# 23Octubre.net
KiCad netlist of a schematic drawn in EAGLE
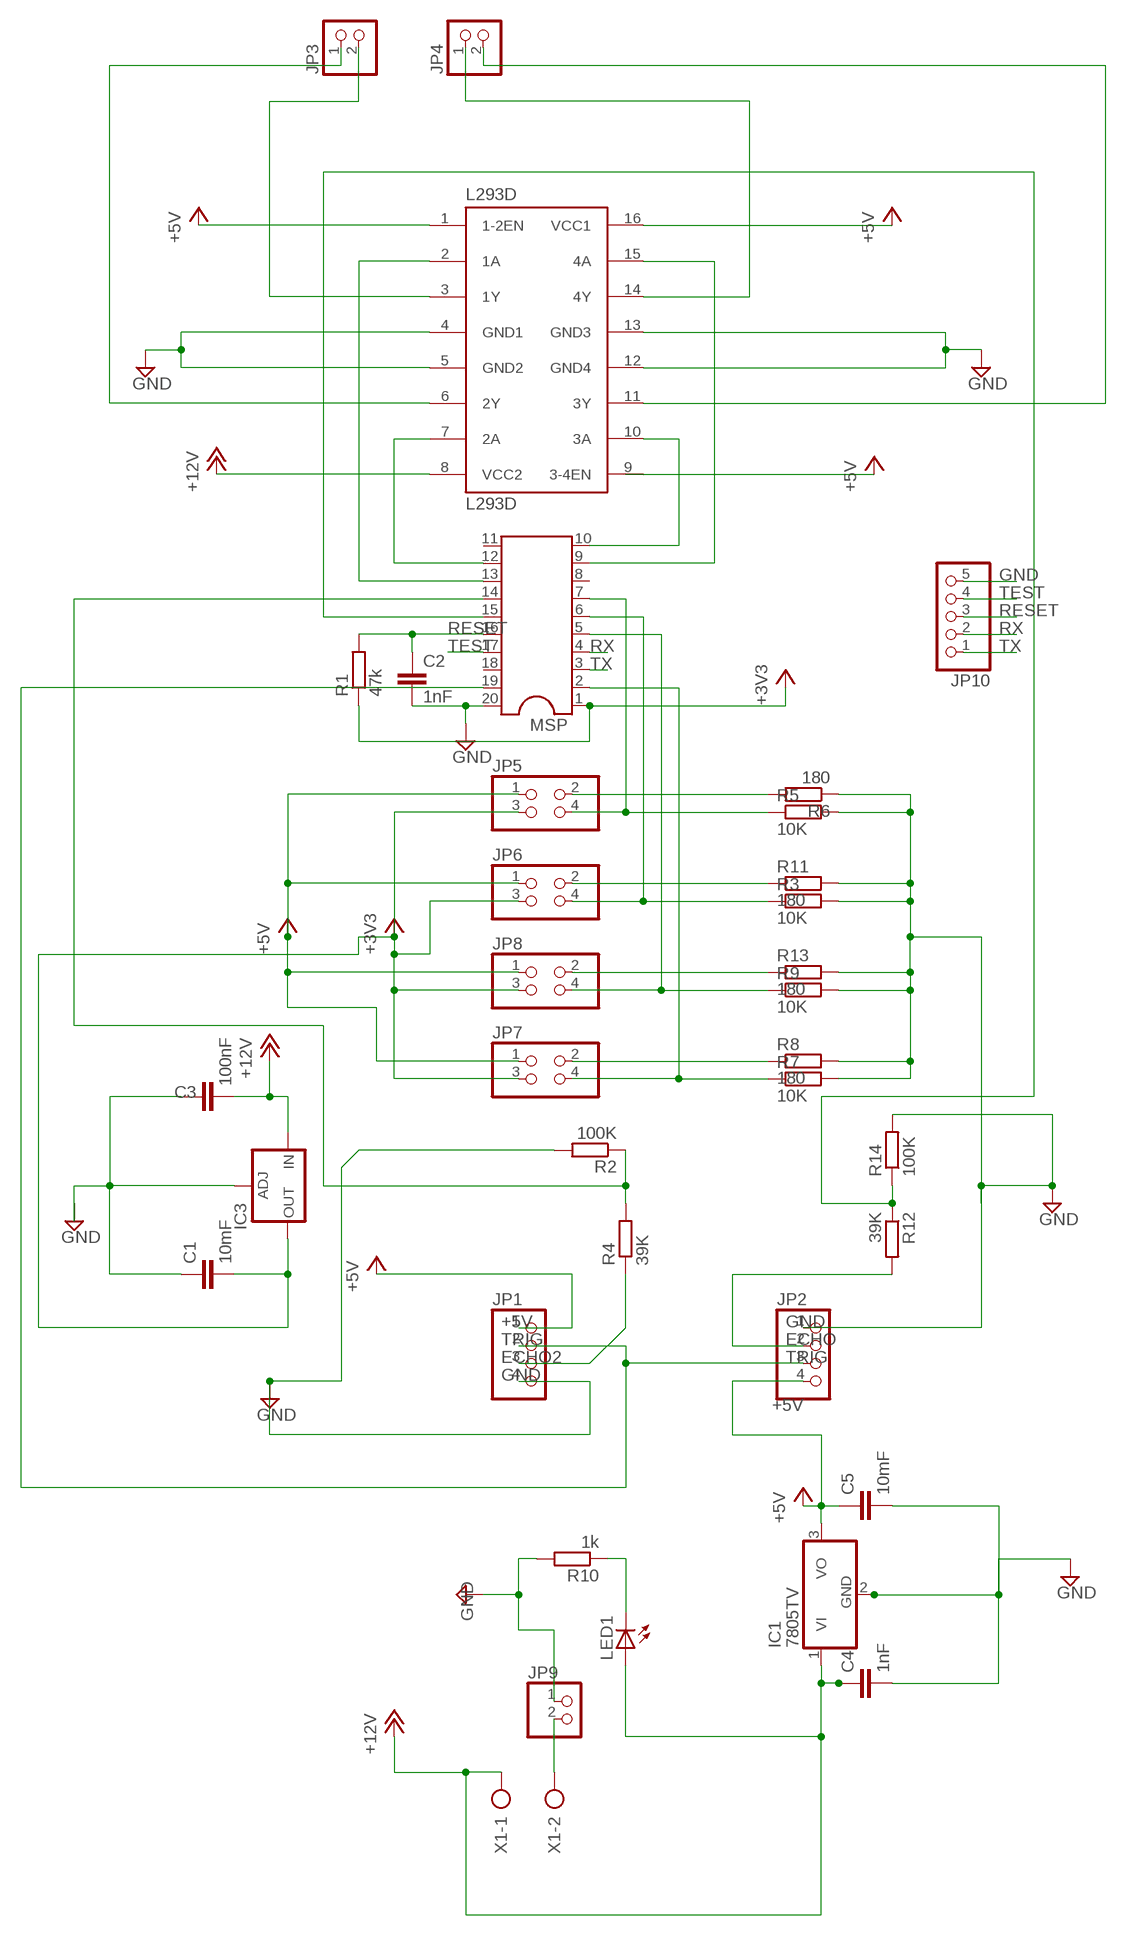
[diagram p0: schematic, sheet 1]

(export (version "E")
  (design (tool "Eeschema 10.0.6"))
  (components
    (comp (ref "C1")
      (value "10mF")
      (footprint "eagle-import:C050-025X075")
      (libsource (lib "eagle-import") (part "C-EU050-025X075"))
    )
    (comp (ref "C2")
      (value "1nF")
      (footprint "eagle-import:C050-025X075")
      (libsource (lib "eagle-import") (part "C-EU050-025X075"))
    )
    (comp (ref "C3")
      (value "100nF")
      (footprint "eagle-import:C050-025X075")
      (libsource (lib "eagle-import") (part "C-EU050-025X075"))
    )
    (comp (ref "C4")
      (value "1nF")
      (footprint "eagle-import:C050-025X075")
      (libsource (lib "eagle-import") (part "C-EU050-025X075"))
    )
    (comp (ref "C5")
      (value "10mF")
      (footprint "eagle-import:C050-025X075")
      (libsource (lib "eagle-import") (part "C-EU050-025X075"))
    )
    (comp (ref "IC1")
      (value "7805TV")
      (footprint "eagle-import:TO220V")
      (libsource (lib "eagle-import") (part "78TV05"))
    )
    (comp (ref "IC3")
      (value "LM317TS")
      (footprint "eagle-import:317TS")
      (libsource (lib "eagle-import") (part "LM317TS"))
    )
    (comp (ref "JP1")
      (value "PINHD-1X4")
      (footprint "eagle-import:1X04")
      (libsource (lib "eagle-import") (part "PINHD-1X4"))
    )
    (comp (ref "JP2")
      (value "PINHD-1X4")
      (footprint "eagle-import:1X04")
      (libsource (lib "eagle-import") (part "PINHD-1X4"))
    )
    (comp (ref "JP3")
      (value "PINHD-1X2")
      (footprint "eagle-import:1X02")
      (libsource (lib "eagle-import") (part "PINHD-1X2"))
    )
    (comp (ref "JP4")
      (value "PINHD-1X2")
      (footprint "eagle-import:1X02")
      (libsource (lib "eagle-import") (part "PINHD-1X2"))
    )
    (comp (ref "JP5")
      (value "PINHD-2X2")
      (footprint "eagle-import:2X02")
      (libsource (lib "eagle-import") (part "PINHD-2X2"))
    )
    (comp (ref "JP6")
      (value "PINHD-2X2")
      (footprint "eagle-import:2X02")
      (libsource (lib "eagle-import") (part "PINHD-2X2"))
    )
    (comp (ref "JP7")
      (value "PINHD-2X2")
      (footprint "eagle-import:2X02")
      (libsource (lib "eagle-import") (part "PINHD-2X2"))
    )
    (comp (ref "JP8")
      (value "PINHD-2X2")
      (footprint "eagle-import:2X02")
      (libsource (lib "eagle-import") (part "PINHD-2X2"))
    )
    (comp (ref "JP9")
      (value "PINHD-1X2")
      (footprint "eagle-import:1X02")
      (libsource (lib "eagle-import") (part "PINHD-1X2"))
    )
    (comp (ref "JP10")
      (value "PINHD-1X5")
      (footprint "eagle-import:1X05")
      (libsource (lib "eagle-import") (part "PINHD-1X5"))
    )
    (comp (ref "L293D")
      (value "L293D")
      (footprint "eagle-import:DIL16")
      (libsource (lib "eagle-import") (part "L293D"))
    )
    (comp (ref "LED1")
      (value "LED5MM")
      (footprint "eagle-import:LED5MM")
      (libsource (lib "eagle-import") (part "LED5MM"))
    )
    (comp (ref "MSP")
      (value "DIL20")
      (footprint "eagle-import:DIL20")
      (libsource (lib "eagle-import") (part "DIL20"))
    )
    (comp (ref "R1")
      (value "47k")
      (footprint "eagle-import:0207_10")
      (libsource (lib "eagle-import") (part "R-EU_0207/10"))
    )
    (comp (ref "R2")
      (value "100K")
      (footprint "eagle-import:0207_10")
      (libsource (lib "eagle-import") (part "R-EU_0207/10"))
    )
    (comp (ref "R3")
      (value "10K")
      (footprint "eagle-import:0207_10")
      (libsource (lib "eagle-import") (part "R-EU_0207/10"))
    )
    (comp (ref "R4")
      (value "39K")
      (footprint "eagle-import:0207_10")
      (libsource (lib "eagle-import") (part "R-EU_0207/10"))
    )
    (comp (ref "R5")
      (value "10K")
      (footprint "eagle-import:0207_10")
      (libsource (lib "eagle-import") (part "R-EU_0207/10"))
    )
    (comp (ref "R6")
      (value "180")
      (footprint "eagle-import:0207_10")
      (libsource (lib "eagle-import") (part "R-EU_0207/10"))
    )
    (comp (ref "R7")
      (value "10K")
      (footprint "eagle-import:0207_10")
      (libsource (lib "eagle-import") (part "R-EU_0207/10"))
    )
    (comp (ref "R8")
      (value "180")
      (footprint "eagle-import:0207_10")
      (libsource (lib "eagle-import") (part "R-EU_0207/10"))
    )
    (comp (ref "R9")
      (value "10K")
      (footprint "eagle-import:0207_10")
      (libsource (lib "eagle-import") (part "R-EU_0207/10"))
    )
    (comp (ref "R10")
      (value "1k")
      (footprint "eagle-import:0207_10")
      (libsource (lib "eagle-import") (part "R-EU_0207/10"))
    )
    (comp (ref "R11")
      (value "180")
      (footprint "eagle-import:0207_10")
      (libsource (lib "eagle-import") (part "R-EU_0207/10"))
    )
    (comp (ref "R12")
      (value "39K")
      (footprint "eagle-import:0207_10")
      (libsource (lib "eagle-import") (part "R-EU_0207/10"))
    )
    (comp (ref "R13")
      (value "180")
      (footprint "eagle-import:0207_10")
      (libsource (lib "eagle-import") (part "R-EU_0207/10"))
    )
    (comp (ref "R14")
      (value "100K")
      (footprint "eagle-import:0207_10")
      (libsource (lib "eagle-import") (part "R-EU_0207/10"))
    )
    (comp (ref "X1")
      (value "AK300/2")
      (footprint "eagle-import:AK300_2")
      (libsource (lib "eagle-import") (part "AK300/2"))
    )
  )
  (nets
    (net (code "1") (name "+3V3") (class "Default")
      (node (ref "C1") (pin "2") (pinfunction "2_2") (pintype "passive"))
      (node (ref "IC3") (pin "2") (pinfunction "OUT_2") (pintype "passive"))
      (node (ref "JP5") (pin "3") (pinfunction "3_3") (pintype "passive"))
      (node (ref "JP6") (pin "3") (pinfunction "3_3") (pintype "passive"))
      (node (ref "JP7") (pin "3") (pinfunction "3_3") (pintype "passive"))
      (node (ref "JP8") (pin "3") (pinfunction "3_3") (pintype "passive"))
      (node (ref "MSP") (pin "1") (pinfunction "1_1") (pintype "passive"))
      (node (ref "R1") (pin "1") (pinfunction "1_1") (pintype "passive"))
    )
    (net (code "2") (name "+5V") (class "Default")
      (node (ref "C5") (pin "1") (pinfunction "1_1") (pintype "passive"))
      (node (ref "IC1") (pin "3") (pinfunction "VO_3") (pintype "passive"))
      (node (ref "JP1") (pin "1") (pinfunction "1_1") (pintype "passive"))
      (node (ref "JP2") (pin "4") (pinfunction "4_4") (pintype "passive"))
      (node (ref "JP5") (pin "1") (pinfunction "1_1") (pintype "passive"))
      (node (ref "JP6") (pin "1") (pinfunction "1_1") (pintype "passive"))
      (node (ref "JP7") (pin "1") (pinfunction "1_1") (pintype "passive"))
      (node (ref "JP8") (pin "1") (pinfunction "1_1") (pintype "passive"))
      (node (ref "L293D") (pin "1") (pinfunction "1-2EN_1") (pintype "input"))
      (node (ref "L293D") (pin "16") (pinfunction "VCC1_16") (pintype "power_in"))
      (node (ref "L293D") (pin "9") (pinfunction "3-4EN_9") (pintype "input"))
    )
    (net (code "3") (name "+12V") (class "Default")
      (node (ref "C3") (pin "2") (pinfunction "2_2") (pintype "passive"))
      (node (ref "C4") (pin "1") (pinfunction "1_1") (pintype "passive"))
      (node (ref "IC1") (pin "1") (pinfunction "VI_1") (pintype "input"))
      (node (ref "IC3") (pin "3") (pinfunction "IN_3") (pintype "input"))
      (node (ref "L293D") (pin "8") (pinfunction "VCC2_8") (pintype "power_in"))
      (node (ref "LED1") (pin "A") (pinfunction "A_A") (pintype "passive"))
      (node (ref "X1") (pin "1") (pinfunction "KL_1") (pintype "passive"))
    )
    (net (code "4") (name "/ECHO") (class "Default")
      (node (ref "JP2") (pin "2") (pinfunction "2_2") (pintype "passive"))
      (node (ref "R12") (pin "2") (pinfunction "2_2") (pintype "passive"))
    )
    (net (code "5") (name "/ECHO2") (class "Default")
      (node (ref "JP1") (pin "3") (pinfunction "3_3") (pintype "passive"))
      (node (ref "R4") (pin "1") (pinfunction "1_1") (pintype "passive"))
    )
    (net (code "6") (name "/RESET") (class "Default")
      (node (ref "C2") (pin "1") (pinfunction "1_1") (pintype "passive"))
      (node (ref "JP10") (pin "3") (pinfunction "3_3") (pintype "passive"))
      (node (ref "MSP") (pin "16") (pinfunction "16_16") (pintype "passive"))
      (node (ref "R1") (pin "2") (pinfunction "2_2") (pintype "passive"))
    )
    (net (code "7") (name "/RX") (class "Default")
      (node (ref "JP10") (pin "2") (pinfunction "2_2") (pintype "passive"))
      (node (ref "MSP") (pin "4") (pinfunction "4_4") (pintype "passive"))
    )
    (net (code "8") (name "/TEST") (class "Default")
      (node (ref "JP10") (pin "4") (pinfunction "4_4") (pintype "passive"))
      (node (ref "MSP") (pin "17") (pinfunction "17_17") (pintype "passive"))
    )
    (net (code "9") (name "/TRIG") (class "Default")
      (node (ref "JP1") (pin "2") (pinfunction "2_2") (pintype "passive"))
      (node (ref "JP2") (pin "3") (pinfunction "3_3") (pintype "passive"))
      (node (ref "MSP") (pin "19") (pinfunction "19_19") (pintype "passive"))
    )
    (net (code "10") (name "/TX") (class "Default")
      (node (ref "JP10") (pin "1") (pinfunction "1_1") (pintype "passive"))
      (node (ref "MSP") (pin "3") (pinfunction "3_3") (pintype "passive"))
    )
    (net (code "11") (name "GND") (class "Default")
      (node (ref "C1") (pin "1") (pinfunction "1_1") (pintype "passive"))
      (node (ref "C2") (pin "2") (pinfunction "2_2") (pintype "passive"))
      (node (ref "C3") (pin "1") (pinfunction "1_1") (pintype "passive"))
      (node (ref "C4") (pin "2") (pinfunction "2_2") (pintype "passive"))
      (node (ref "C5") (pin "2") (pinfunction "2_2") (pintype "passive"))
      (node (ref "IC1") (pin "2") (pinfunction "GND_2") (pintype "passive"))
      (node (ref "IC3") (pin "1") (pinfunction "ADJ_1") (pintype "input"))
      (node (ref "JP1") (pin "4") (pinfunction "4_4") (pintype "passive"))
      (node (ref "JP10") (pin "5") (pinfunction "5_5") (pintype "passive"))
      (node (ref "JP2") (pin "1") (pinfunction "1_1") (pintype "passive"))
      (node (ref "JP9") (pin "1") (pinfunction "1_1") (pintype "passive"))
      (node (ref "L293D") (pin "12") (pinfunction "GND4_12") (pintype "power_in"))
      (node (ref "L293D") (pin "13") (pinfunction "GND3_13") (pintype "power_in"))
      (node (ref "L293D") (pin "4") (pinfunction "GND1_4") (pintype "power_in"))
      (node (ref "L293D") (pin "5") (pinfunction "GND2_5") (pintype "power_in"))
      (node (ref "MSP") (pin "20") (pinfunction "20_20") (pintype "passive"))
      (node (ref "R10") (pin "2") (pinfunction "2_2") (pintype "passive"))
      (node (ref "R11") (pin "2") (pinfunction "2_2") (pintype "passive"))
      (node (ref "R13") (pin "2") (pinfunction "2_2") (pintype "passive"))
      (node (ref "R14") (pin "2") (pinfunction "2_2") (pintype "passive"))
      (node (ref "R2") (pin "2") (pinfunction "2_2") (pintype "passive"))
      (node (ref "R3") (pin "2") (pinfunction "2_2") (pintype "passive"))
      (node (ref "R5") (pin "2") (pinfunction "2_2") (pintype "passive"))
      (node (ref "R6") (pin "1") (pinfunction "1_1") (pintype "passive"))
      (node (ref "R7") (pin "2") (pinfunction "2_2") (pintype "passive"))
      (node (ref "R8") (pin "2") (pinfunction "2_2") (pintype "passive"))
      (node (ref "R9") (pin "2") (pinfunction "2_2") (pintype "passive"))
    )
    (net (code "12") (name "Net-(JP5-Pad2)") (class "Default")
      (node (ref "JP5") (pin "2") (pinfunction "2_2") (pintype "passive"))
      (node (ref "R6") (pin "2") (pinfunction "2_2") (pintype "passive"))
    )
    (net (code "13") (name "Net-(JP5-Pad4)") (class "Default")
      (node (ref "JP5") (pin "4") (pinfunction "4_4") (pintype "passive"))
      (node (ref "MSP") (pin "7") (pinfunction "7_7") (pintype "passive"))
      (node (ref "R5") (pin "1") (pinfunction "1_1") (pintype "passive"))
    )
    (net (code "14") (name "Net-(JP6-Pad2)") (class "Default")
      (node (ref "JP6") (pin "2") (pinfunction "2_2") (pintype "passive"))
      (node (ref "R11") (pin "1") (pinfunction "1_1") (pintype "passive"))
    )
    (net (code "15") (name "Net-(JP6-Pad4)") (class "Default")
      (node (ref "JP6") (pin "4") (pinfunction "4_4") (pintype "passive"))
      (node (ref "MSP") (pin "6") (pinfunction "6_6") (pintype "passive"))
      (node (ref "R3") (pin "1") (pinfunction "1_1") (pintype "passive"))
    )
    (net (code "16") (name "Net-(JP7-Pad2)") (class "Default")
      (node (ref "JP7") (pin "2") (pinfunction "2_2") (pintype "passive"))
      (node (ref "R8") (pin "1") (pinfunction "1_1") (pintype "passive"))
    )
    (net (code "17") (name "Net-(JP7-Pad4)") (class "Default")
      (node (ref "JP7") (pin "4") (pinfunction "4_4") (pintype "passive"))
      (node (ref "MSP") (pin "2") (pinfunction "2_2") (pintype "passive"))
      (node (ref "R7") (pin "1") (pinfunction "1_1") (pintype "passive"))
    )
    (net (code "18") (name "Net-(JP8-Pad2)") (class "Default")
      (node (ref "JP8") (pin "2") (pinfunction "2_2") (pintype "passive"))
      (node (ref "R13") (pin "1") (pinfunction "1_1") (pintype "passive"))
    )
    (net (code "19") (name "Net-(JP8-Pad4)") (class "Default")
      (node (ref "JP8") (pin "4") (pinfunction "4_4") (pintype "passive"))
      (node (ref "MSP") (pin "5") (pinfunction "5_5") (pintype "passive"))
      (node (ref "R9") (pin "1") (pinfunction "1_1") (pintype "passive"))
    )
    (net (code "20") (name "Net-(L293D-1A)") (class "Default")
      (node (ref "L293D") (pin "2") (pinfunction "1A_2") (pintype "input"))
      (node (ref "MSP") (pin "13") (pinfunction "13_13") (pintype "passive"))
    )
    (net (code "21") (name "Net-(L293D-1Y)") (class "Default")
      (node (ref "JP3") (pin "2") (pinfunction "2_2") (pintype "passive"))
      (node (ref "L293D") (pin "3") (pinfunction "1Y_3") (pintype "output"))
    )
    (net (code "22") (name "Net-(L293D-2A)") (class "Default")
      (node (ref "L293D") (pin "7") (pinfunction "2A_7") (pintype "input"))
      (node (ref "MSP") (pin "12") (pinfunction "12_12") (pintype "passive"))
    )
    (net (code "23") (name "Net-(L293D-2Y)") (class "Default")
      (node (ref "JP3") (pin "1") (pinfunction "1_1") (pintype "passive"))
      (node (ref "L293D") (pin "6") (pinfunction "2Y_6") (pintype "output"))
    )
    (net (code "24") (name "Net-(L293D-3A)") (class "Default")
      (node (ref "L293D") (pin "10") (pinfunction "3A_10") (pintype "input"))
      (node (ref "MSP") (pin "10") (pinfunction "10_10") (pintype "passive"))
    )
    (net (code "25") (name "Net-(L293D-3Y)") (class "Default")
      (node (ref "JP4") (pin "2") (pinfunction "2_2") (pintype "passive"))
      (node (ref "L293D") (pin "11") (pinfunction "3Y_11") (pintype "output"))
    )
    (net (code "26") (name "Net-(L293D-4A)") (class "Default")
      (node (ref "L293D") (pin "15") (pinfunction "4A_15") (pintype "input"))
      (node (ref "MSP") (pin "9") (pinfunction "9_9") (pintype "passive"))
    )
    (net (code "27") (name "Net-(L293D-4Y)") (class "Default")
      (node (ref "JP4") (pin "1") (pinfunction "1_1") (pintype "passive"))
      (node (ref "L293D") (pin "14") (pinfunction "4Y_14") (pintype "output"))
    )
    (net (code "28") (name "Net-(LED1-C)") (class "Default")
      (node (ref "LED1") (pin "K") (pinfunction "C_K") (pintype "passive"))
      (node (ref "R10") (pin "1") (pinfunction "1_1") (pintype "passive"))
    )
    (net (code "29") (name "Net-(MSP-Pad14)") (class "Default")
      (node (ref "MSP") (pin "14") (pinfunction "14_14") (pintype "passive"))
      (node (ref "R2") (pin "1") (pinfunction "1_1") (pintype "passive"))
      (node (ref "R4") (pin "2") (pinfunction "2_2") (pintype "passive"))
    )
    (net (code "30") (name "Net-(MSP-Pad15)") (class "Default")
      (node (ref "MSP") (pin "15") (pinfunction "15_15") (pintype "passive"))
      (node (ref "R12") (pin "1") (pinfunction "1_1") (pintype "passive"))
      (node (ref "R14") (pin "1") (pinfunction "1_1") (pintype "passive"))
    )
    (net (code "31") (name "Net-(X1B-KL)") (class "Default")
      (node (ref "JP9") (pin "2") (pinfunction "2_2") (pintype "passive"))
      (node (ref "X1") (pin "2") (pinfunction "KL_2") (pintype "passive"))
    )
    (net (code "32") (name "unconnected-(MSP-Pad8)") (class "Default")
      (node (ref "MSP") (pin "8") (pinfunction "8_8") (pintype "passive"))
    )
    (net (code "33") (name "unconnected-(MSP-Pad11)") (class "Default")
      (node (ref "MSP") (pin "11") (pinfunction "11_11") (pintype "passive"))
    )
    (net (code "34") (name "unconnected-(MSP-Pad18)") (class "Default")
      (node (ref "MSP") (pin "18") (pinfunction "18_18") (pintype "passive"))
    )
  )
)
